# STM32_DDS.net
KiCad netlist of a schematic drawn in Altium Designer
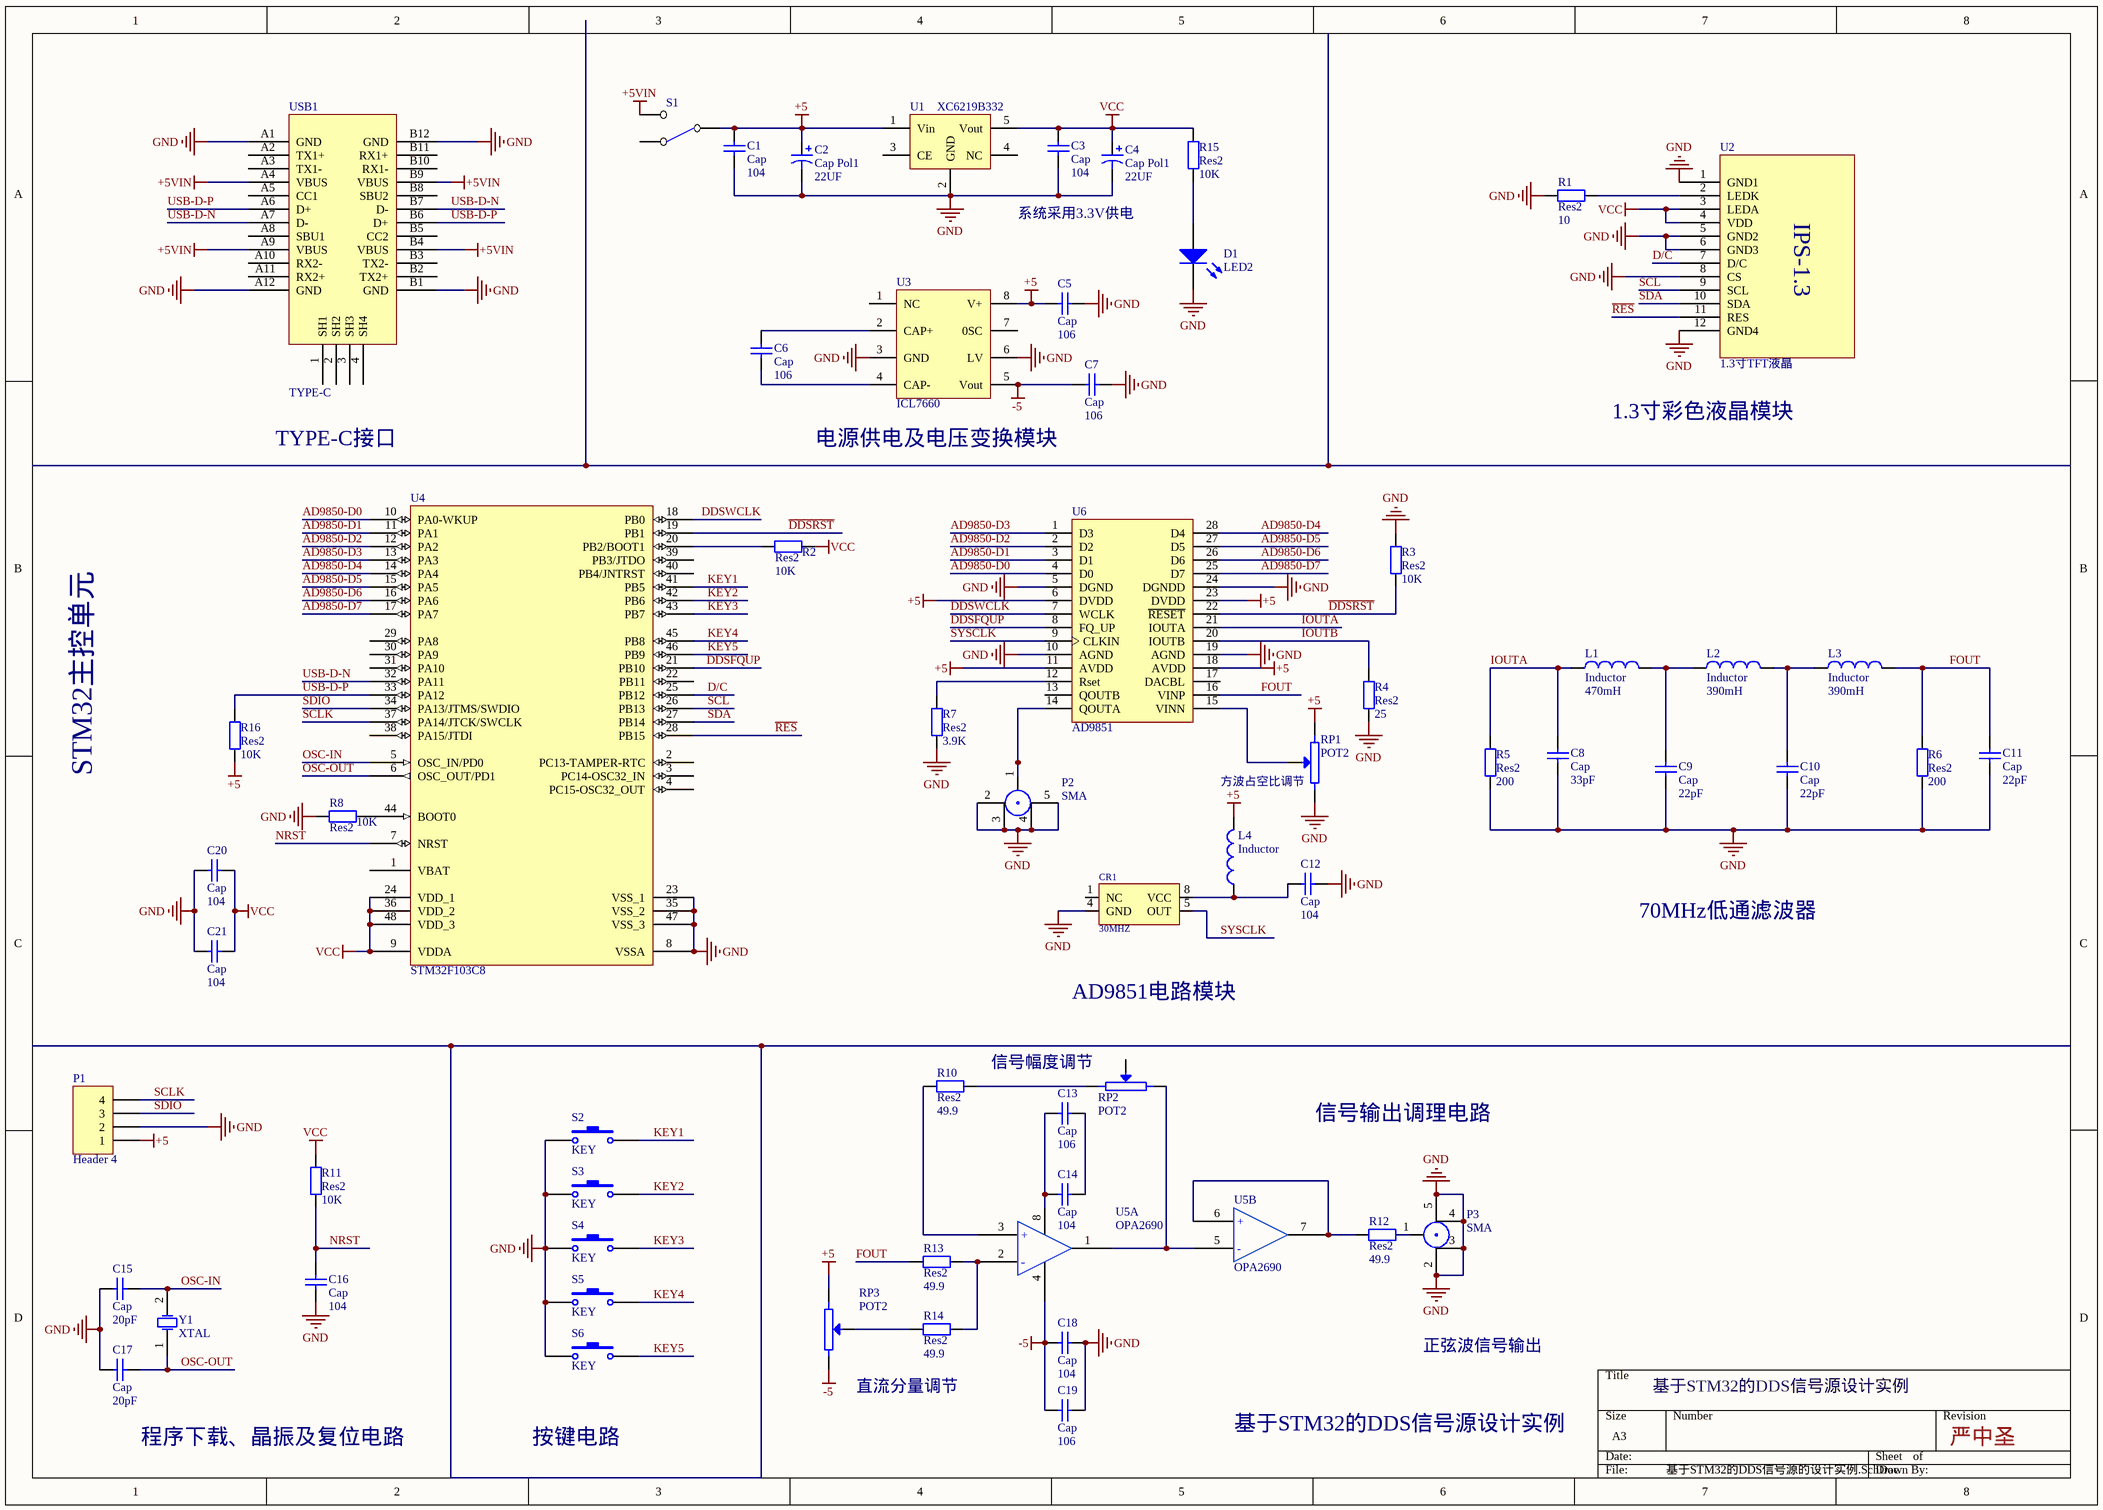
[diagram p0: 基于STM32的DDS信号源的设计实例.SchDoc]

(export (version "E")
  (design (tool "Eeschema 10.0.6"))
  (components
    (comp (ref "C1")
      (value "Cap")
      (footprint "RAD-0.3")
      (description "Capacitor")
      (fields (field (name "ALTIUM_VALUE") "104") (field (name "PUBLISHER") "Altium Limited"))
      (libsource (lib "Miscellaneous Devices") (part "Cap"))
    )
    (comp (ref "C2")
      (value "Cap Pol1")
      (footprint "RB7.6-15")
      (description "Polarized Capacitor (Radial)")
      (fields (field (name "ALTIUM_VALUE") "22UF") (field (name "PUBLISHER") "Altium Limited"))
      (libsource (lib "Miscellaneous Devices") (part "Cap Pol1"))
    )
    (comp (ref "C3")
      (value "Cap")
      (footprint "RAD-0.3")
      (description "Capacitor")
      (fields (field (name "ALTIUM_VALUE") "104") (field (name "PUBLISHER") "Altium Limited"))
      (libsource (lib "Miscellaneous Devices") (part "Cap"))
    )
    (comp (ref "C4")
      (value "Cap Pol1")
      (footprint "RB7.6-15")
      (description "Polarized Capacitor (Radial)")
      (fields (field (name "ALTIUM_VALUE") "22UF") (field (name "PUBLISHER") "Altium Limited"))
      (libsource (lib "Miscellaneous Devices") (part "Cap Pol1"))
    )
    (comp (ref "C5")
      (value "Cap")
      (footprint "RAD-0.3")
      (description "Capacitor")
      (fields (field (name "ALTIUM_VALUE") "106") (field (name "PUBLISHER") "Altium Limited"))
      (libsource (lib "Miscellaneous Devices") (part "Cap"))
    )
    (comp (ref "C6")
      (value "Cap")
      (footprint "RAD-0.3")
      (description "Capacitor")
      (fields (field (name "ALTIUM_VALUE") "106") (field (name "PUBLISHER") "Altium Limited"))
      (libsource (lib "Miscellaneous Devices") (part "Cap"))
    )
    (comp (ref "C7")
      (value "Cap")
      (footprint "RAD-0.3")
      (description "Capacitor")
      (fields (field (name "ALTIUM_VALUE") "106") (field (name "PUBLISHER") "Altium Limited"))
      (libsource (lib "Miscellaneous Devices") (part "Cap"))
    )
    (comp (ref "C8")
      (value "Cap")
      (footprint "RAD-0.3")
      (description "Capacitor")
      (fields (field (name "ALTIUM_VALUE") "33pF") (field (name "PUBLISHER") "Altium Limited"))
      (libsource (lib "Miscellaneous Devices") (part "Cap"))
    )
    (comp (ref "C9")
      (value "Cap")
      (footprint "RAD-0.3")
      (description "Capacitor")
      (fields (field (name "ALTIUM_VALUE") "22pF") (field (name "PUBLISHER") "Altium Limited"))
      (libsource (lib "Miscellaneous Devices") (part "Cap"))
    )
    (comp (ref "C10")
      (value "Cap")
      (footprint "RAD-0.3")
      (description "Capacitor")
      (fields (field (name "ALTIUM_VALUE") "22pF") (field (name "PUBLISHER") "Altium Limited"))
      (libsource (lib "Miscellaneous Devices") (part "Cap"))
    )
    (comp (ref "C11")
      (value "Cap")
      (footprint "RAD-0.3")
      (description "Capacitor")
      (fields (field (name "ALTIUM_VALUE") "22pF") (field (name "PUBLISHER") "Altium Limited"))
      (libsource (lib "Miscellaneous Devices") (part "Cap"))
    )
    (comp (ref "C12")
      (value "Cap")
      (footprint "RAD-0.3")
      (description "Capacitor")
      (fields (field (name "ALTIUM_VALUE") "104") (field (name "PUBLISHER") "Altium Limited"))
      (libsource (lib "Miscellaneous Devices") (part "Cap"))
    )
    (comp (ref "C13")
      (value "Cap")
      (footprint "RAD-0.3")
      (description "Capacitor")
      (fields (field (name "ALTIUM_VALUE") "106") (field (name "PUBLISHER") "Altium Limited"))
      (libsource (lib "Miscellaneous Devices") (part "Cap"))
    )
    (comp (ref "C14")
      (value "Cap")
      (footprint "RAD-0.3")
      (description "Capacitor")
      (fields (field (name "ALTIUM_VALUE") "104") (field (name "PUBLISHER") "Altium Limited"))
      (libsource (lib "Miscellaneous Devices") (part "Cap"))
    )
    (comp (ref "C15")
      (value "Cap")
      (footprint "RAD-0.3")
      (description "Capacitor")
      (fields (field (name "ALTIUM_VALUE") "20pF") (field (name "PUBLISHER") "Altium Limited"))
      (libsource (lib "Miscellaneous Devices") (part "Cap"))
    )
    (comp (ref "C16")
      (value "Cap")
      (footprint "RAD-0.3")
      (description "Capacitor")
      (fields (field (name "ALTIUM_VALUE") "104") (field (name "PUBLISHER") "Altium Limited"))
      (libsource (lib "Miscellaneous Devices") (part "Cap"))
    )
    (comp (ref "C17")
      (value "Cap")
      (footprint "RAD-0.3")
      (description "Capacitor")
      (fields (field (name "ALTIUM_VALUE") "20pF") (field (name "PUBLISHER") "Altium Limited"))
      (libsource (lib "Miscellaneous Devices") (part "Cap"))
    )
    (comp (ref "C18")
      (value "Cap")
      (footprint "RAD-0.3")
      (description "Capacitor")
      (fields (field (name "ALTIUM_VALUE") "104") (field (name "PUBLISHER") "Altium Limited"))
      (libsource (lib "Miscellaneous Devices") (part "Cap"))
    )
    (comp (ref "C19")
      (value "Cap")
      (footprint "RAD-0.3")
      (description "Capacitor")
      (fields (field (name "ALTIUM_VALUE") "106") (field (name "PUBLISHER") "Altium Limited"))
      (libsource (lib "Miscellaneous Devices") (part "Cap"))
    )
    (comp (ref "C20")
      (value "Cap")
      (footprint "RAD-0.3")
      (description "Capacitor")
      (fields (field (name "ALTIUM_VALUE") "104") (field (name "PUBLISHER") "Altium Limited"))
      (libsource (lib "Miscellaneous Devices") (part "Cap"))
    )
    (comp (ref "C21")
      (value "Cap")
      (footprint "RAD-0.3")
      (description "Capacitor")
      (fields (field (name "ALTIUM_VALUE") "104") (field (name "PUBLISHER") "Altium Limited"))
      (libsource (lib "Miscellaneous Devices") (part "Cap"))
    )
    (comp (ref "CR1")
      (value "30MHZ")
      (footprint "CRYSTAL-SMT-5X7")
      (libsource (lib "基于STM32的DDS信号源设计实例") (part "CRYSTAL-DIP8"))
    )
    (comp (ref "D1")
      (value "LED2")
      (footprint "3.2X1.6X1.1")
      (description "Typical RED, GREEN, YELLOW, AMBER GaAs LED")
      (fields (field (name "PUBLISHER") "Altium Limited"))
      (libsource (lib "Miscellaneous Devices") (part "LED2"))
    )
    (comp (ref "L1")
      (value "Inductor")
      (footprint "0402-A")
      (fields (field (name "ALTIUM_VALUE") "470mH") (field (name "PUBLISHER") "Altium Limited"))
      (libsource (lib "Miscellaneous Devices") (part "Inductor"))
    )
    (comp (ref "L2")
      (value "Inductor")
      (footprint "0402-A")
      (fields (field (name "ALTIUM_VALUE") "390mH") (field (name "PUBLISHER") "Altium Limited"))
      (libsource (lib "Miscellaneous Devices") (part "Inductor"))
    )
    (comp (ref "L3")
      (value "Inductor")
      (footprint "0402-A")
      (fields (field (name "ALTIUM_VALUE") "390mH") (field (name "PUBLISHER") "Altium Limited"))
      (libsource (lib "Miscellaneous Devices") (part "Inductor"))
    )
    (comp (ref "L4")
      (value "Inductor")
      (footprint "6-0805_N")
      (fields (field (name "PUBLISHER") "Altium Limited"))
      (libsource (lib "基于STM32的DDS信号源设计实例") (part "Inductor"))
    )
    (comp (ref "P1")
      (value "Header 4")
      (footprint "HDR1X4")
      (description "Header, 4-Pin")
      (fields (field (name "PUBLISHER") "Altium Limited"))
      (libsource (lib "Miscellaneous Connectors") (part "Header 4"))
    )
    (comp (ref "P2") (value "SMA") (footprint "SMA-KE") (libsource (lib "原理图库") (part "SMA")))
    (comp (ref "P3") (value "SMA") (footprint "SMA-KE") (libsource (lib "原理图库") (part "SMA")))
    (comp (ref "R1")
      (value "Res2")
      (footprint "AXIAL-0.4")
      (description "Resistor")
      (fields (field (name "ALTIUM_VALUE") "10") (field (name "PUBLISHER") "Altium Limited"))
      (libsource (lib "Miscellaneous Devices") (part "Res2"))
    )
    (comp (ref "R2")
      (value "Res2")
      (footprint "AXIAL-0.4")
      (description "Resistor")
      (fields (field (name "ALTIUM_VALUE") "10K") (field (name "PUBLISHER") "Altium Limited"))
      (libsource (lib "Miscellaneous Devices") (part "Res2"))
    )
    (comp (ref "R3")
      (value "Res2")
      (footprint "AXIAL-0.4")
      (description "Resistor")
      (fields (field (name "ALTIUM_VALUE") "10K") (field (name "PUBLISHER") "Altium Limited"))
      (libsource (lib "") (part "Res2_1"))
    )
    (comp (ref "R4")
      (value "Res2")
      (footprint "AXIAL-0.4")
      (description "Resistor")
      (fields (field (name "ALTIUM_VALUE") "25") (field (name "PUBLISHER") "Altium Limited"))
      (libsource (lib "") (part "Res2_1"))
    )
    (comp (ref "R5")
      (value "Res2")
      (footprint "AXIAL-0.4")
      (description "Resistor")
      (fields (field (name "ALTIUM_VALUE") "200") (field (name "PUBLISHER") "Altium Limited"))
      (libsource (lib "") (part "Res2_1"))
    )
    (comp (ref "R6")
      (value "Res2")
      (footprint "AXIAL-0.4")
      (description "Resistor")
      (fields (field (name "ALTIUM_VALUE") "200") (field (name "PUBLISHER") "Altium Limited"))
      (libsource (lib "") (part "Res2_1"))
    )
    (comp (ref "R7")
      (value "Res2")
      (footprint "AXIAL-0.4")
      (description "Resistor")
      (fields (field (name "ALTIUM_VALUE") "3.9K") (field (name "PUBLISHER") "Altium Limited"))
      (libsource (lib "") (part "Res2_1"))
    )
    (comp (ref "R8")
      (value "Res2")
      (footprint "AXIAL-0.4")
      (description "Resistor")
      (fields (field (name "ALTIUM_VALUE") "10K") (field (name "PUBLISHER") "Altium Limited"))
      (libsource (lib "Miscellaneous Devices") (part "Res2"))
    )
    (comp (ref "R10")
      (value "Res2")
      (footprint "AXIAL-0.4")
      (description "Resistor")
      (fields (field (name "ALTIUM_VALUE") "49.9") (field (name "PUBLISHER") "Altium Limited"))
      (libsource (lib "Miscellaneous Devices") (part "Res2"))
    )
    (comp (ref "R11")
      (value "Res2")
      (footprint "AXIAL-0.4")
      (description "Resistor")
      (fields (field (name "ALTIUM_VALUE") "10K") (field (name "PUBLISHER") "Altium Limited"))
      (libsource (lib "") (part "Res2_1"))
    )
    (comp (ref "R12")
      (value "Res2")
      (footprint "AXIAL-0.4")
      (description "Resistor")
      (fields (field (name "ALTIUM_VALUE") "49.9") (field (name "PUBLISHER") "Altium Limited"))
      (libsource (lib "Miscellaneous Devices") (part "Res2"))
    )
    (comp (ref "R13")
      (value "Res2")
      (footprint "AXIAL-0.4")
      (description "Resistor")
      (fields (field (name "ALTIUM_VALUE") "49.9") (field (name "PUBLISHER") "Altium Limited"))
      (libsource (lib "Miscellaneous Devices") (part "Res2"))
    )
    (comp (ref "R14")
      (value "Res2")
      (footprint "AXIAL-0.4")
      (description "Resistor")
      (fields (field (name "ALTIUM_VALUE") "49.9") (field (name "PUBLISHER") "Altium Limited"))
      (libsource (lib "Miscellaneous Devices") (part "Res2"))
    )
    (comp (ref "R15")
      (value "Res2")
      (footprint "AXIAL-0.4")
      (description "Resistor")
      (fields (field (name "ALTIUM_VALUE") "10K") (field (name "PUBLISHER") "Altium Limited"))
      (libsource (lib "") (part "Res2_1"))
    )
    (comp (ref "R16")
      (value "Res2")
      (footprint "AXIAL-0.4")
      (description "Resistor")
      (fields (field (name "ALTIUM_VALUE") "10K") (field (name "PUBLISHER") "Altium Limited"))
      (libsource (lib "") (part "Res2_1"))
    )
    (comp (ref "RP1")
      (value "POT2")
      (footprint "VR7")
      (description "Potentiometer")
      (libsource (lib "基于STM32的DDS信号源设计实例") (part "POT2"))
    )
    (comp (ref "RP2")
      (value "POT2")
      (footprint "VR7")
      (description "Potentiometer")
      (libsource (lib "基于STM32的DDS信号源设计实例") (part "POT2"))
    )
    (comp (ref "RP3")
      (value "POT2")
      (footprint "VR7")
      (description "Potentiometer")
      (libsource (lib "基于STM32的DDS信号源设计实例") (part "POT2"))
    )
    (comp (ref "S1")
      (value "~")
      (footprint "SW-SPDT-7P")
      (libsource (lib "基于STM32的DDS信号源设计实例") (part "SW SPDT"))
    )
    (comp (ref "S2")
      (value "KEY")
      (footprint "SW-MINI")
      (description "Switch")
      (fields (field (name "PUBLISHER") "Altium Limited"))
      (libsource (lib "基于STM32的DDS信号源设计实例") (part "SW-PB"))
    )
    (comp (ref "S3")
      (value "KEY")
      (footprint "SW-MINI")
      (description "Switch")
      (fields (field (name "PUBLISHER") "Altium Limited"))
      (libsource (lib "基于STM32的DDS信号源设计实例") (part "SW-PB"))
    )
    (comp (ref "S4")
      (value "KEY")
      (footprint "SW-MINI")
      (description "Switch")
      (fields (field (name "PUBLISHER") "Altium Limited"))
      (libsource (lib "基于STM32的DDS信号源设计实例") (part "SW-PB"))
    )
    (comp (ref "S5")
      (value "KEY")
      (footprint "SW-MINI")
      (description "Switch")
      (fields (field (name "PUBLISHER") "Altium Limited"))
      (libsource (lib "基于STM32的DDS信号源设计实例") (part "SW-PB"))
    )
    (comp (ref "S6")
      (value "KEY")
      (footprint "SW-MINI")
      (description "Switch")
      (fields (field (name "PUBLISHER") "Altium Limited"))
      (libsource (lib "基于STM32的DDS信号源设计实例") (part "SW-PB"))
    )
    (comp (ref "U1")
      (value "XC6219B332")
      (footprint "SOT23-5L")
      (libsource (lib "基于STM32的DDS信号源设计实例") (part "XC6219"))
    )
    (comp (ref "U2")
      (value "1.3寸TFT液晶")
      (footprint "1.3-TFT-TPS")
      (libsource (lib "基于STM32的DDS信号源设计实例") (part "1.3寸TFT液晶"))
    )
    (comp (ref "U3")
      (value "ICL7660")
      (footprint "SO-8")
      (libsource (lib "基于STM32的DDS信号源设计实例") (part "ICL7660"))
    )
    (comp (ref "U4")
      (value "STM32F103C8")
      (footprint "TQFP-48")
      (description "Flaah:64/RAM:20/IO:36")
      (fields (field (name "版权归属") "源创客"))
      (libsource (lib "基于STM32的DDS信号源设计实例") (part "STM32F103C8"))
    )
    (comp (ref "U5") (value "OPA2690") (footprint "SO-8") (libsource (lib "原理图库") (part "OPA2690")))
    (comp (ref "U6") (value "AD9851") (footprint "TSSOP28") (libsource (lib "原理图库") (part "AD9851")))
    (comp (ref "USB1")
      (value "TYPE-C")
      (footprint "TYPE-C")
      (libsource (lib "基于STM32的DDS信号源设计实例") (part "TYPE-C"))
    )
    (comp (ref "Y1")
      (value "XTAL")
      (footprint "R38")
      (description "Crystal Oscillator")
      (fields (field (name "PUBLISHER") "Altium Limited"))
      (libsource (lib "Miscellaneous Devices") (part "XTAL"))
    )
  )
  (nets
    (net (code "1") (name "+5") (class "Default")
      (node (ref "C1") (pin "2") (pinfunction "2_2") (pintype "passive"))
      (node (ref "C2") (pin "1") (pinfunction "1_1") (pintype "passive"))
      (node (ref "C5") (pin "1") (pinfunction "1_1") (pintype "passive"))
      (node (ref "L4") (pin "2") (pinfunction "2_2") (pintype "passive"))
      (node (ref "P1") (pin "1") (pinfunction "1_1") (pintype "passive"))
      (node (ref "R16") (pin "1") (pinfunction "1_1") (pintype "passive"))
      (node (ref "RP1") (pin "2") (pinfunction "2_2") (pintype "passive"))
      (node (ref "RP3") (pin "1") (pinfunction "1_1") (pintype "passive"))
      (node (ref "S1") (pin "2") (pinfunction "COMMON_2") (pintype "passive"))
      (node (ref "U1") (pin "1") (pinfunction "Vin_1") (pintype "passive"))
      (node (ref "U3") (pin "8") (pinfunction "V+_8") (pintype "passive"))
      (node (ref "U6") (pin "11") (pinfunction "AVDD_11") (pintype "passive"))
      (node (ref "U6") (pin "18") (pinfunction "AVDD_18") (pintype "passive"))
      (node (ref "U6") (pin "23") (pinfunction "DVDD_23") (pintype "passive"))
      (node (ref "U6") (pin "6") (pinfunction "DVDD_6") (pintype "passive"))
    )
    (net (code "2") (name "+5VIN") (class "Default")
      (node (ref "S1") (pin "3") (pinfunction "NO_3") (pintype "passive"))
      (node (ref "USB1") (pin "A4") (pinfunction "VBUS_A4") (pintype "passive"))
      (node (ref "USB1") (pin "A9") (pinfunction "VBUS_A9") (pintype "passive"))
      (node (ref "USB1") (pin "B4") (pinfunction "VBUS_B4") (pintype "passive"))
      (node (ref "USB1") (pin "B9") (pinfunction "VBUS_B9") (pintype "passive"))
    )
    (net (code "3") (name "-5") (class "Default")
      (node (ref "C18") (pin "2") (pinfunction "2_2") (pintype "passive"))
      (node (ref "C19") (pin "2") (pinfunction "2_2") (pintype "passive"))
      (node (ref "C7") (pin "1") (pinfunction "1_1") (pintype "passive"))
      (node (ref "RP3") (pin "2") (pinfunction "2_2") (pintype "passive"))
      (node (ref "U3") (pin "5") (pinfunction "Vout_5") (pintype "passive"))
      (node (ref "U5") (pin "4") (pinfunction "4_4") (pintype "passive"))
    )
    (net (code "4") (name "/AD9850-D0") (class "Default")
      (node (ref "U4") (pin "10") (pinfunction "PA0-WKUP_10") (pintype "bidirectional"))
      (node (ref "U6") (pin "4") (pinfunction "D0_4") (pintype "passive"))
    )
    (net (code "5") (name "/AD9850-D1") (class "Default")
      (node (ref "U4") (pin "11") (pinfunction "PA1_11") (pintype "bidirectional"))
      (node (ref "U6") (pin "3") (pinfunction "D1_3") (pintype "passive"))
    )
    (net (code "6") (name "/AD9850-D2") (class "Default")
      (node (ref "U4") (pin "12") (pinfunction "PA2_12") (pintype "bidirectional"))
      (node (ref "U6") (pin "2") (pinfunction "D2_2") (pintype "passive"))
    )
    (net (code "7") (name "/AD9850-D3") (class "Default")
      (node (ref "U4") (pin "13") (pinfunction "PA3_13") (pintype "bidirectional"))
      (node (ref "U6") (pin "1") (pinfunction "D3_1") (pintype "passive"))
    )
    (net (code "8") (name "/AD9850-D4") (class "Default")
      (node (ref "U4") (pin "14") (pinfunction "PA4_14") (pintype "bidirectional"))
      (node (ref "U6") (pin "28") (pinfunction "D4_28") (pintype "passive"))
    )
    (net (code "9") (name "/AD9850-D5") (class "Default")
      (node (ref "U4") (pin "15") (pinfunction "PA5_15") (pintype "bidirectional"))
      (node (ref "U6") (pin "27") (pinfunction "D5_27") (pintype "passive"))
    )
    (net (code "10") (name "/AD9850-D6") (class "Default")
      (node (ref "U4") (pin "16") (pinfunction "PA6_16") (pintype "bidirectional"))
      (node (ref "U6") (pin "26") (pinfunction "D6_26") (pintype "passive"))
    )
    (net (code "11") (name "/AD9850-D7") (class "Default")
      (node (ref "U4") (pin "17") (pinfunction "PA7_17") (pintype "bidirectional"))
      (node (ref "U6") (pin "25") (pinfunction "D7_25") (pintype "passive"))
    )
    (net (code "12") (name "/DDSFQUP") (class "Default")
      (node (ref "U4") (pin "21") (pinfunction "PB10_21") (pintype "bidirectional"))
      (node (ref "U6") (pin "8") (pinfunction "FQ_UP_8") (pintype "passive"))
    )
    (net (code "13") (name "/DDSWCLK") (class "Default")
      (node (ref "U4") (pin "18") (pinfunction "PB0_18") (pintype "bidirectional"))
      (node (ref "U6") (pin "7") (pinfunction "WCLK_7") (pintype "passive"))
    )
    (net (code "14") (name "/D{slash}C") (class "Default")
      (node (ref "U2") (pin "7") (pinfunction "D/C_7") (pintype "passive"))
      (node (ref "U4") (pin "25") (pinfunction "PB12_25") (pintype "bidirectional"))
    )
    (net (code "15") (name "/FOUT") (class "Default")
      (node (ref "C11") (pin "2") (pinfunction "2_2") (pintype "passive"))
      (node (ref "L3") (pin "2") (pinfunction "2_2") (pintype "passive"))
      (node (ref "R13") (pin "1") (pinfunction "1_1") (pintype "passive"))
      (node (ref "R6") (pin "2") (pinfunction "2_2") (pintype "passive"))
      (node (ref "U6") (pin "16") (pinfunction "VINP_16") (pintype "passive"))
    )
    (net (code "16") (name "/IOUTA") (class "Default")
      (node (ref "C8") (pin "2") (pinfunction "2_2") (pintype "passive"))
      (node (ref "L1") (pin "1") (pinfunction "1_1") (pintype "passive"))
      (node (ref "R5") (pin "2") (pinfunction "2_2") (pintype "passive"))
      (node (ref "U6") (pin "21") (pinfunction "IOUTA_21") (pintype "passive"))
    )
    (net (code "17") (name "/IOUTB") (class "Default")
      (node (ref "R4") (pin "2") (pinfunction "2_2") (pintype "passive"))
      (node (ref "U6") (pin "20") (pinfunction "IOUTB_20") (pintype "passive"))
    )
    (net (code "18") (name "/KEY1") (class "Default")
      (node (ref "S2") (pin "2") (pinfunction "2_2") (pintype "passive"))
      (node (ref "U4") (pin "41") (pinfunction "PB5_41") (pintype "bidirectional"))
    )
    (net (code "19") (name "/KEY2") (class "Default")
      (node (ref "S3") (pin "2") (pinfunction "2_2") (pintype "passive"))
      (node (ref "U4") (pin "42") (pinfunction "PB6_42") (pintype "bidirectional"))
    )
    (net (code "20") (name "/KEY3") (class "Default")
      (node (ref "S4") (pin "2") (pinfunction "2_2") (pintype "passive"))
      (node (ref "U4") (pin "43") (pinfunction "PB7_43") (pintype "bidirectional"))
    )
    (net (code "21") (name "/KEY4") (class "Default")
      (node (ref "S5") (pin "2") (pinfunction "2_2") (pintype "passive"))
      (node (ref "U4") (pin "45") (pinfunction "PB8_45") (pintype "bidirectional"))
    )
    (net (code "22") (name "/KEY5") (class "Default")
      (node (ref "S6") (pin "2") (pinfunction "2_2") (pintype "passive"))
      (node (ref "U4") (pin "46") (pinfunction "PB9_46") (pintype "bidirectional"))
    )
    (net (code "23") (name "/NRST") (class "Default")
      (node (ref "C16") (pin "2") (pinfunction "2_2") (pintype "passive"))
      (node (ref "R11") (pin "1") (pinfunction "1_1") (pintype "passive"))
      (node (ref "U4") (pin "7") (pinfunction "NRST_7") (pintype "bidirectional"))
    )
    (net (code "24") (name "/OSC-IN") (class "Default")
      (node (ref "C15") (pin "2") (pinfunction "2_2") (pintype "passive"))
      (node (ref "U4") (pin "5") (pinfunction "OSC_IN/PD0_5") (pintype "input"))
      (node (ref "Y1") (pin "2") (pinfunction "OSC2_2") (pintype "passive"))
    )
    (net (code "25") (name "/OSC-OUT") (class "Default")
      (node (ref "C17") (pin "2") (pinfunction "2_2") (pintype "passive"))
      (node (ref "U4") (pin "6") (pinfunction "OSC_OUT/PD1_6") (pintype "output"))
      (node (ref "Y1") (pin "1") (pinfunction "OSC1_1") (pintype "passive"))
    )
    (net (code "26") (name "/SCL") (class "Default")
      (node (ref "U2") (pin "9") (pinfunction "SCL_9") (pintype "passive"))
      (node (ref "U4") (pin "26") (pinfunction "PB13_26") (pintype "bidirectional"))
    )
    (net (code "27") (name "/SCLK") (class "Default")
      (node (ref "P1") (pin "4") (pinfunction "4_4") (pintype "passive"))
      (node (ref "U4") (pin "37") (pinfunction "PA14/JTCK/SWCLK_37") (pintype "bidirectional"))
    )
    (net (code "28") (name "/SDA") (class "Default")
      (node (ref "U2") (pin "10") (pinfunction "SDA_10") (pintype "passive"))
      (node (ref "U4") (pin "27") (pinfunction "PB14_27") (pintype "bidirectional"))
    )
    (net (code "29") (name "/SDIO") (class "Default")
      (node (ref "P1") (pin "3") (pinfunction "3_3") (pintype "passive"))
      (node (ref "U4") (pin "34") (pinfunction "PA13/JTMS/SWDIO_34") (pintype "bidirectional"))
    )
    (net (code "30") (name "/SYSCLK") (class "Default")
      (node (ref "CR1") (pin "5") (pinfunction "OUT_5") (pintype "passive"))
      (node (ref "U6") (pin "9") (pinfunction "CLKIN_9") (pintype "passive"))
    )
    (net (code "31") (name "/USB-D-N") (class "Default")
      (node (ref "U4") (pin "32") (pinfunction "PA11_32") (pintype "bidirectional"))
      (node (ref "USB1") (pin "A7") (pinfunction "D-_A7") (pintype "passive"))
      (node (ref "USB1") (pin "B7") (pinfunction "D-_B7") (pintype "passive"))
    )
    (net (code "32") (name "/USB-D-P") (class "Default")
      (node (ref "R16") (pin "2") (pinfunction "2_2") (pintype "passive"))
      (node (ref "U4") (pin "33") (pinfunction "PA12_33") (pintype "bidirectional"))
      (node (ref "USB1") (pin "A6") (pinfunction "D+_A6") (pintype "passive"))
      (node (ref "USB1") (pin "B6") (pinfunction "D+_B6") (pintype "passive"))
    )
    (net (code "33") (name "/~{DDSRST}") (class "Default")
      (node (ref "R3") (pin "1") (pinfunction "1_1") (pintype "passive"))
      (node (ref "U4") (pin "19") (pinfunction "PB1_19") (pintype "bidirectional"))
      (node (ref "U6") (pin "22") (pinfunction "~{RESET}_22") (pintype "passive"))
    )
    (net (code "34") (name "/~{RES}") (class "Default")
      (node (ref "U2") (pin "11") (pinfunction "RES_11") (pintype "passive"))
      (node (ref "U4") (pin "28") (pinfunction "PB15_28") (pintype "bidirectional"))
    )
    (net (code "35") (name "GND") (class "Default")
      (node (ref "C1") (pin "1") (pinfunction "1_1") (pintype "passive"))
      (node (ref "C10") (pin "1") (pinfunction "1_1") (pintype "passive"))
      (node (ref "C11") (pin "1") (pinfunction "1_1") (pintype "passive"))
      (node (ref "C12") (pin "2") (pinfunction "2_2") (pintype "passive"))
      (node (ref "C15") (pin "1") (pinfunction "1_1") (pintype "passive"))
      (node (ref "C16") (pin "1") (pinfunction "1_1") (pintype "passive"))
      (node (ref "C17") (pin "1") (pinfunction "1_1") (pintype "passive"))
      (node (ref "C18") (pin "1") (pinfunction "1_1") (pintype "passive"))
      (node (ref "C19") (pin "1") (pinfunction "1_1") (pintype "passive"))
      (node (ref "C2") (pin "2") (pinfunction "2_2") (pintype "passive"))
      (node (ref "C20") (pin "1") (pinfunction "1_1") (pintype "passive"))
      (node (ref "C21") (pin "1") (pinfunction "1_1") (pintype "passive"))
      (node (ref "C3") (pin "1") (pinfunction "1_1") (pintype "passive"))
      (node (ref "C4") (pin "2") (pinfunction "2_2") (pintype "passive"))
      (node (ref "C5") (pin "2") (pinfunction "2_2") (pintype "passive"))
      (node (ref "C7") (pin "2") (pinfunction "2_2") (pintype "passive"))
      (node (ref "C8") (pin "1") (pinfunction "1_1") (pintype "passive"))
      (node (ref "C9") (pin "1") (pinfunction "1_1") (pintype "passive"))
      (node (ref "CR1") (pin "4") (pinfunction "GND_4") (pintype "passive"))
      (node (ref "D1") (pin "2") (pinfunction "K_2") (pintype "passive"))
      (node (ref "P1") (pin "2") (pinfunction "2_2") (pintype "passive"))
      (node (ref "P2") (pin "2") (pinfunction "2_2") (pintype "passive"))
      (node (ref "P2") (pin "3") (pinfunction "1_3") (pintype "passive"))
      (node (ref "P2") (pin "4") (pinfunction "2_4") (pintype "passive"))
      (node (ref "P2") (pin "5") (pinfunction "3_5") (pintype "passive"))
      (node (ref "P3") (pin "2") (pinfunction "2_2") (pintype "passive"))
      (node (ref "P3") (pin "3") (pinfunction "1_3") (pintype "passive"))
      (node (ref "P3") (pin "4") (pinfunction "2_4") (pintype "passive"))
      (node (ref "P3") (pin "5") (pinfunction "3_5") (pintype "passive"))
      (node (ref "R1") (pin "1") (pinfunction "1_1") (pintype "passive"))
      (node (ref "R3") (pin "2") (pinfunction "2_2") (pintype "passive"))
      (node (ref "R4") (pin "1") (pinfunction "1_1") (pintype "passive"))
      (node (ref "R5") (pin "1") (pinfunction "1_1") (pintype "passive"))
      (node (ref "R6") (pin "1") (pinfunction "1_1") (pintype "passive"))
      (node (ref "R7") (pin "1") (pinfunction "1_1") (pintype "passive"))
      (node (ref "R8") (pin "1") (pinfunction "1_1") (pintype "passive"))
      (node (ref "RP1") (pin "1") (pinfunction "1_1") (pintype "passive"))
      (node (ref "S2") (pin "1") (pinfunction "1_1") (pintype "passive"))
      (node (ref "S3") (pin "1") (pinfunction "1_1") (pintype "passive"))
      (node (ref "S4") (pin "1") (pinfunction "1_1") (pintype "passive"))
      (node (ref "S5") (pin "1") (pinfunction "1_1") (pintype "passive"))
      (node (ref "S6") (pin "1") (pinfunction "1_1") (pintype "passive"))
      (node (ref "U1") (pin "2") (pinfunction "GND_2") (pintype "power_in"))
      (node (ref "U2") (pin "1") (pinfunction "GND1_1") (pintype "passive"))
      (node (ref "U2") (pin "12") (pinfunction "GND4_12") (pintype "passive"))
      (node (ref "U2") (pin "5") (pinfunction "GND2_5") (pintype "passive"))
      (node (ref "U2") (pin "6") (pinfunction "GND3_6") (pintype "passive"))
      (node (ref "U2") (pin "8") (pinfunction "CS_8") (pintype "passive"))
      (node (ref "U3") (pin "3") (pinfunction "GND_3") (pintype "passive"))
      (node (ref "U3") (pin "6") (pinfunction "LV_6") (pintype "passive"))
      (node (ref "U4") (pin "23") (pinfunction "VSS_1_23") (pintype "power_in"))
      (node (ref "U4") (pin "35") (pinfunction "VSS_2_35") (pintype "power_in"))
      (node (ref "U4") (pin "47") (pinfunction "VSS_3_47") (pintype "power_in"))
      (node (ref "U4") (pin "8") (pinfunction "VSSA_8") (pintype "power_in"))
      (node (ref "U6") (pin "10") (pinfunction "AGND_10") (pintype "passive"))
      (node (ref "U6") (pin "19") (pinfunction "AGND_19") (pintype "passive"))
      (node (ref "U6") (pin "24") (pinfunction "DGNDD_24") (pintype "passive"))
      (node (ref "U6") (pin "5") (pinfunction "DGND_5") (pintype "passive"))
      (node (ref "USB1") (pin "A1") (pinfunction "GND_A1") (pintype "passive"))
      (node (ref "USB1") (pin "A12") (pinfunction "GND_A12") (pintype "passive"))
      (node (ref "USB1") (pin "B1") (pinfunction "GND_B1") (pintype "passive"))
      (node (ref "USB1") (pin "B12") (pinfunction "GND_B12") (pintype "passive"))
    )
    (net (code "36") (name "Net-(C9-Pad2)") (class "Default")
      (node (ref "C9") (pin "2") (pinfunction "2_2") (pintype "passive"))
      (node (ref "L1") (pin "2") (pinfunction "2_2") (pintype "passive"))
      (node (ref "L2") (pin "1") (pinfunction "1_1") (pintype "passive"))
    )
    (net (code "37") (name "Net-(C10-Pad2)") (class "Default")
      (node (ref "C10") (pin "2") (pinfunction "2_2") (pintype "passive"))
      (node (ref "L2") (pin "2") (pinfunction "2_2") (pintype "passive"))
      (node (ref "L3") (pin "1") (pinfunction "1_1") (pintype "passive"))
    )
    (net (code "38") (name "Net-(C13-Pad1)") (class "Default")
      (node (ref "C13") (pin "1") (pinfunction "1_1") (pintype "passive"))
      (node (ref "C14") (pin "1") (pinfunction "1_1") (pintype "passive"))
    )
    (net (code "39") (name "Net-(C13-Pad2)") (class "Default")
      (node (ref "C13") (pin "2") (pinfunction "2_2") (pintype "passive"))
      (node (ref "C14") (pin "2") (pinfunction "2_2") (pintype "passive"))
      (node (ref "U5") (pin "8") (pintype "passive"))
    )
    (net (code "40") (name "Net-(CR1-VCC)") (class "Default")
      (node (ref "C12") (pin "1") (pinfunction "1_1") (pintype "passive"))
      (node (ref "CR1") (pin "8") (pinfunction "VCC_8") (pintype "passive"))
      (node (ref "L4") (pin "1") (pinfunction "1_1") (pintype "passive"))
    )
    (net (code "41") (name "Net-(D1-A)") (class "Default")
      (node (ref "D1") (pin "1") (pinfunction "A_1") (pintype "passive"))
      (node (ref "R15") (pin "1") (pinfunction "1_1") (pintype "passive"))
    )
    (net (code "42") (name "Net-(P2-0)") (class "Default")
      (node (ref "P2") (pin "1") (pinfunction "0_1") (pintype "passive"))
      (node (ref "U6") (pin "14") (pinfunction "QOUTA_14") (pintype "passive"))
    )
    (net (code "43") (name "Net-(P3-0)") (class "Default")
      (node (ref "P3") (pin "1") (pinfunction "0_1") (pintype "passive"))
      (node (ref "R12") (pin "2") (pinfunction "2_2") (pintype "passive"))
    )
    (net (code "44") (name "Net-(R10-Pad2)") (class "Default")
      (node (ref "R10") (pin "2") (pinfunction "2_2") (pintype "passive"))
      (node (ref "RP2") (pin "1") (pinfunction "1_1") (pintype "passive"))
    )
    (net (code "45") (name "Net-(R14-Pad1)") (class "Default")
      (node (ref "R14") (pin "1") (pinfunction "1_1") (pintype "passive"))
      (node (ref "RP3") (pin "3") (pinfunction "3_3") (pintype "passive"))
    )
    (net (code "46") (name "Net-(U2-LEDK)") (class "Default")
      (node (ref "R1") (pin "2") (pinfunction "2_2") (pintype "passive"))
      (node (ref "U2") (pin "2") (pinfunction "LEDK_2") (pintype "passive"))
    )
    (net (code "47") (name "Net-(U3-CAP+)") (class "Default")
      (node (ref "C6") (pin "1") (pinfunction "1_1") (pintype "passive"))
      (node (ref "U3") (pin "2") (pinfunction "CAP+_2") (pintype "passive"))
    )
    (net (code "48") (name "Net-(U3-CAP-)") (class "Default")
      (node (ref "C6") (pin "2") (pinfunction "2_2") (pintype "passive"))
      (node (ref "U3") (pin "4") (pinfunction "CAP-_4") (pintype "passive"))
    )
    (net (code "49") (name "Net-(U4-BOOT0)") (class "Default")
      (node (ref "R8") (pin "2") (pinfunction "2_2") (pintype "passive"))
      (node (ref "U4") (pin "44") (pinfunction "BOOT0_44") (pintype "input"))
    )
    (net (code "50") (name "Net-(U4-PB2{slash}BOOT1)") (class "Default")
      (node (ref "R2") (pin "1") (pinfunction "1_1") (pintype "passive"))
      (node (ref "U4") (pin "20") (pinfunction "PB2/BOOT1_20") (pintype "bidirectional"))
    )
    (net (code "51") (name "Net-(U5A-+)") (class "Default")
      (node (ref "R10") (pin "1") (pinfunction "1_1") (pintype "passive"))
      (node (ref "U5") (pin "3") (pinfunction "+_3") (pintype "passive"))
    )
    (net (code "52") (name "Net-(U5A--)") (class "Default")
      (node (ref "R13") (pin "2") (pinfunction "2_2") (pintype "passive"))
      (node (ref "R14") (pin "2") (pinfunction "2_2") (pintype "passive"))
      (node (ref "U5") (pin "2") (pinfunction "-_2") (pintype "passive"))
    )
    (net (code "53") (name "Net-(U5B-+)") (class "Default")
      (node (ref "R12") (pin "1") (pinfunction "1_1") (pintype "passive"))
      (node (ref "U5") (pin "6") (pinfunction "+_6") (pintype "passive"))
      (node (ref "U5") (pin "7") (pintype "passive"))
    )
    (net (code "54") (name "Net-(U5B--)") (class "Default")
      (node (ref "RP2") (pin "2") (pinfunction "2_2") (pintype "passive"))
      (node (ref "U5") (pin "1") (pinfunction "1_1") (pintype "passive"))
      (node (ref "U5") (pin "5") (pinfunction "-_5") (pintype "passive"))
    )
    (net (code "55") (name "Net-(U6-Rset)") (class "Default")
      (node (ref "R7") (pin "2") (pinfunction "2_2") (pintype "passive"))
      (node (ref "U6") (pin "12") (pinfunction "Rset_12") (pintype "passive"))
    )
    (net (code "56") (name "Net-(U6-VINN)") (class "Default")
      (node (ref "RP1") (pin "3") (pinfunction "3_3") (pintype "passive"))
      (node (ref "U6") (pin "15") (pinfunction "VINN_15") (pintype "passive"))
    )
    (net (code "57") (name "VCC") (class "Default")
      (node (ref "C20") (pin "2") (pinfunction "2_2") (pintype "passive"))
      (node (ref "C21") (pin "2") (pinfunction "2_2") (pintype "passive"))
      (node (ref "C3") (pin "2") (pinfunction "2_2") (pintype "passive"))
      (node (ref "C4") (pin "1") (pinfunction "1_1") (pintype "passive"))
      (node (ref "R11") (pin "2") (pinfunction "2_2") (pintype "passive"))
      (node (ref "R15") (pin "2") (pinfunction "2_2") (pintype "passive"))
      (node (ref "R2") (pin "2") (pinfunction "2_2") (pintype "passive"))
      (node (ref "U1") (pin "5") (pinfunction "Vout_5") (pintype "passive"))
      (node (ref "U2") (pin "3") (pinfunction "LEDA_3") (pintype "passive"))
      (node (ref "U2") (pin "4") (pinfunction "VDD_4") (pintype "passive"))
      (node (ref "U4") (pin "24") (pinfunction "VDD_1_24") (pintype "power_in"))
      (node (ref "U4") (pin "36") (pinfunction "VDD_2_36") (pintype "power_in"))
      (node (ref "U4") (pin "48") (pinfunction "VDD_3_48") (pintype "power_in"))
      (node (ref "U4") (pin "9") (pinfunction "VDDA_9") (pintype "power_in"))
    )
    (net (code "58") (name "unconnected-(CR1-NC-Pad1)") (class "Default")
      (node (ref "CR1") (pin "1") (pinfunction "NC_1") (pintype "passive"))
    )
    (net (code "59") (name "unconnected-(RP2-Pad3)") (class "Default")
      (node (ref "RP2") (pin "3") (pinfunction "3_3") (pintype "passive"))
    )
    (net (code "60") (name "unconnected-(S1-NC-Pad1)") (class "Default")
      (node (ref "S1") (pin "1") (pinfunction "NC_1") (pintype "passive"))
    )
    (net (code "61") (name "unconnected-(U1-CE-Pad3)") (class "Default")
      (node (ref "U1") (pin "3") (pinfunction "CE_3") (pintype "passive"))
    )
    (net (code "62") (name "unconnected-(U1-NC-Pad4)") (class "Default")
      (node (ref "U1") (pin "4") (pinfunction "NC_4") (pintype "passive"))
    )
    (net (code "63") (name "unconnected-(U3-0SC-Pad7)") (class "Default")
      (node (ref "U3") (pin "7") (pinfunction "0SC_7") (pintype "passive"))
    )
    (net (code "64") (name "unconnected-(U3-NC-Pad1)") (class "Default")
      (node (ref "U3") (pin "1") (pinfunction "NC_1") (pintype "passive"))
    )
    (net (code "65") (name "unconnected-(U4-PA8-Pad29)") (class "Default")
      (node (ref "U4") (pin "29") (pinfunction "PA8_29") (pintype "bidirectional"))
    )
    (net (code "66") (name "unconnected-(U4-PA9-Pad30)") (class "Default")
      (node (ref "U4") (pin "30") (pinfunction "PA9_30") (pintype "bidirectional"))
    )
    (net (code "67") (name "unconnected-(U4-PA10-Pad31)") (class "Default")
      (node (ref "U4") (pin "31") (pinfunction "PA10_31") (pintype "bidirectional"))
    )
    (net (code "68") (name "unconnected-(U4-PA15{slash}JTDI-Pad38)") (class "Default")
      (node (ref "U4") (pin "38") (pinfunction "PA15/JTDI_38") (pintype "bidirectional"))
    )
    (net (code "69") (name "unconnected-(U4-PB3{slash}JTDO-Pad39)") (class "Default")
      (node (ref "U4") (pin "39") (pinfunction "PB3/JTDO_39") (pintype "bidirectional"))
    )
    (net (code "70") (name "unconnected-(U4-PB4{slash}JNTRST-Pad40)") (class "Default")
      (node (ref "U4") (pin "40") (pinfunction "PB4/JNTRST_40") (pintype "bidirectional"))
    )
    (net (code "71") (name "unconnected-(U4-PB11-Pad22)") (class "Default")
      (node (ref "U4") (pin "22") (pinfunction "PB11_22") (pintype "bidirectional"))
    )
    (net (code "72") (name "unconnected-(U4-PC13-TAMPER-RTC-Pad2)") (class "Default")
      (node (ref "U4") (pin "2") (pinfunction "PC13-TAMPER-RTC_2") (pintype "bidirectional"))
    )
    (net (code "73") (name "unconnected-(U4-PC14-OSC32_IN-Pad3)") (class "Default")
      (node (ref "U4") (pin "3") (pinfunction "PC14-OSC32_IN_3") (pintype "bidirectional"))
    )
    (net (code "74") (name "unconnected-(U4-PC15-OSC32_OUT-Pad4)") (class "Default")
      (node (ref "U4") (pin "4") (pinfunction "PC15-OSC32_OUT_4") (pintype "bidirectional"))
    )
    (net (code "75") (name "unconnected-(U4-VBAT-Pad1)") (class "Default")
      (node (ref "U4") (pin "1") (pinfunction "VBAT_1") (pintype "power_in"))
    )
    (net (code "76") (name "unconnected-(U6-DACBL-Pad17)") (class "Default")
      (node (ref "U6") (pin "17") (pinfunction "DACBL_17") (pintype "passive"))
    )
    (net (code "77") (name "unconnected-(U6-QOUTB-Pad13)") (class "Default")
      (node (ref "U6") (pin "13") (pinfunction "QOUTB_13") (pintype "passive"))
    )
    (net (code "78") (name "unconnected-(USB1-CC1-PadA5)") (class "Default")
      (node (ref "USB1") (pin "A5") (pinfunction "CC1_A5") (pintype "passive"))
    )
    (net (code "79") (name "unconnected-(USB1-CC2-PadB5)") (class "Default")
      (node (ref "USB1") (pin "B5") (pinfunction "CC2_B5") (pintype "passive"))
    )
    (net (code "80") (name "unconnected-(USB1-RX1+-PadB11)") (class "Default")
      (node (ref "USB1") (pin "B11") (pinfunction "RX1+_B11") (pintype "passive"))
    )
    (net (code "81") (name "unconnected-(USB1-RX1--PadB10)") (class "Default")
      (node (ref "USB1") (pin "B10") (pinfunction "RX1-_B10") (pintype "passive"))
    )
    (net (code "82") (name "unconnected-(USB1-RX2+-PadA11)") (class "Default")
      (node (ref "USB1") (pin "A11") (pinfunction "RX2+_A11") (pintype "passive"))
    )
    (net (code "83") (name "unconnected-(USB1-RX2--PadA10)") (class "Default")
      (node (ref "USB1") (pin "A10") (pinfunction "RX2-_A10") (pintype "passive"))
    )
    (net (code "84") (name "unconnected-(USB1-SBU1-PadA8)") (class "Default")
      (node (ref "USB1") (pin "A8") (pinfunction "SBU1_A8") (pintype "passive"))
    )
    (net (code "85") (name "unconnected-(USB1-SBU2-PadB8)") (class "Default")
      (node (ref "USB1") (pin "B8") (pinfunction "SBU2_B8") (pintype "passive"))
    )
    (net (code "86") (name "unconnected-(USB1-SH1-Pad1)") (class "Default")
      (node (ref "USB1") (pin "1") (pinfunction "SH1_1") (pintype "passive"))
    )
    (net (code "87") (name "unconnected-(USB1-SH2-Pad2)") (class "Default")
      (node (ref "USB1") (pin "2") (pinfunction "SH2_2") (pintype "passive"))
    )
    (net (code "88") (name "unconnected-(USB1-SH3-Pad3)") (class "Default")
      (node (ref "USB1") (pin "3") (pinfunction "SH3_3") (pintype "passive"))
    )
    (net (code "89") (name "unconnected-(USB1-SH4-Pad4)") (class "Default")
      (node (ref "USB1") (pin "4") (pinfunction "SH4_4") (pintype "passive"))
    )
    (net (code "90") (name "unconnected-(USB1-TX1+-PadA2)") (class "Default")
      (node (ref "USB1") (pin "A2") (pinfunction "TX1+_A2") (pintype "passive"))
    )
    (net (code "91") (name "unconnected-(USB1-TX1--PadA3)") (class "Default")
      (node (ref "USB1") (pin "A3") (pinfunction "TX1-_A3") (pintype "passive"))
    )
    (net (code "92") (name "unconnected-(USB1-TX2+-PadB2)") (class "Default")
      (node (ref "USB1") (pin "B2") (pinfunction "TX2+_B2") (pintype "passive"))
    )
    (net (code "93") (name "unconnected-(USB1-TX2--PadB3)") (class "Default")
      (node (ref "USB1") (pin "B3") (pinfunction "TX2-_B3") (pintype "passive"))
    )
  )
)
